# OECOC_controlbordroutes.net
KiCad netlist of a schematic drawn in EAGLE
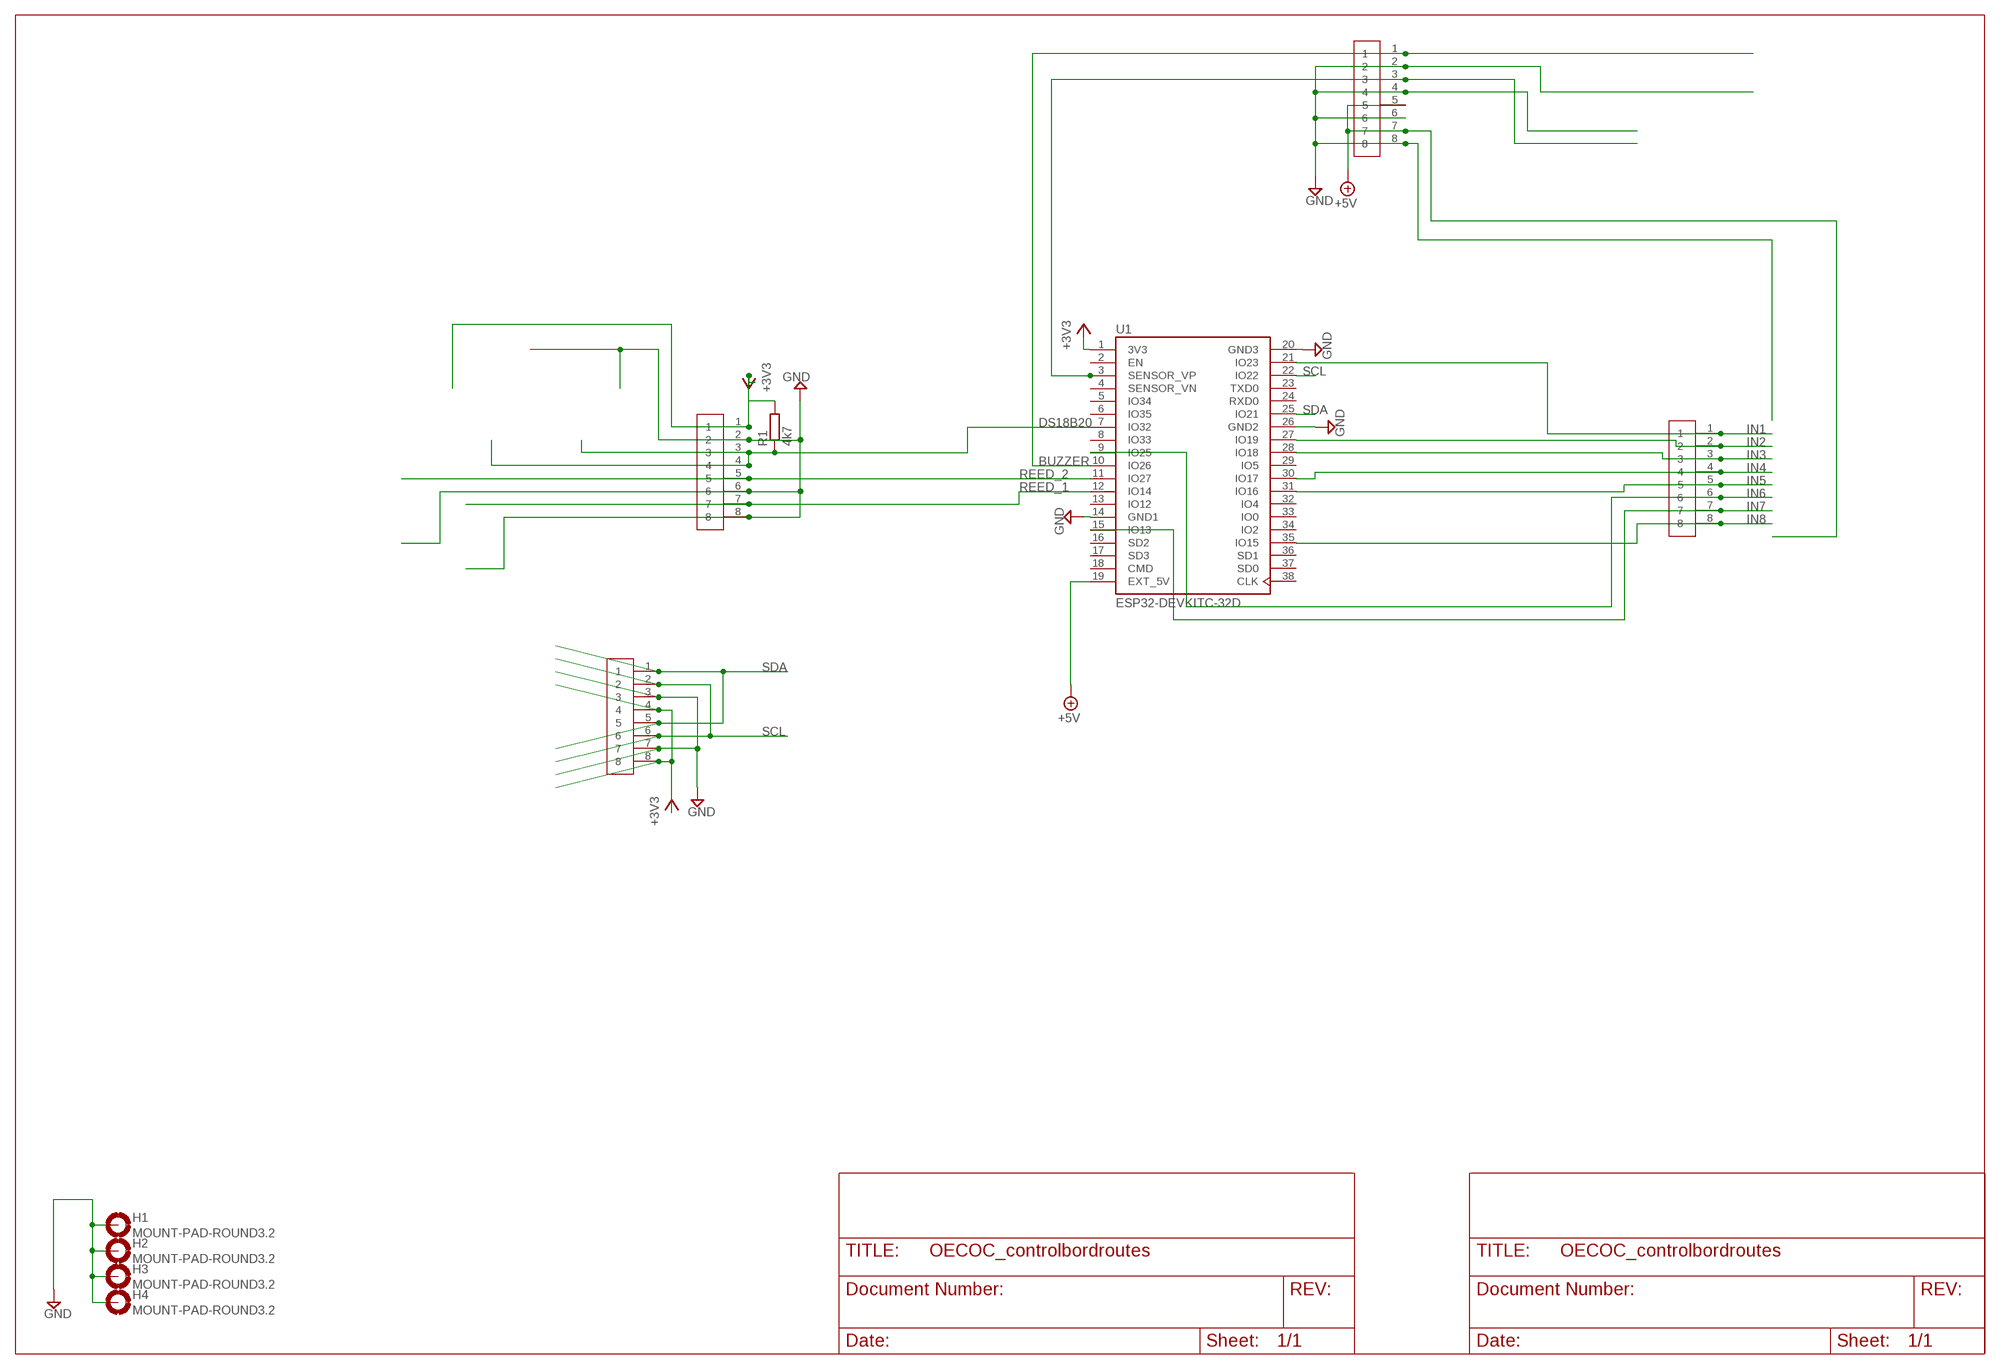
[diagram p0: schematic, sheet 1]

(export (version "E")
  (design (tool "Eeschema 10.0.6"))
  (components
    (comp (ref "H1")
      (value "MOUNT-PAD-ROUND3.2")
      (footprint "eagle-import:3,2-PAD")
      (libsource (lib "eagle-import") (part "MOUNT-PAD-ROUND3.2"))
    )
    (comp (ref "H2")
      (value "MOUNT-PAD-ROUND3.2")
      (footprint "eagle-import:3,2-PAD")
      (libsource (lib "eagle-import") (part "MOUNT-PAD-ROUND3.2"))
    )
    (comp (ref "H3")
      (value "MOUNT-PAD-ROUND3.2")
      (footprint "eagle-import:3,2-PAD")
      (libsource (lib "eagle-import") (part "MOUNT-PAD-ROUND3.2"))
    )
    (comp (ref "H4")
      (value "MOUNT-PAD-ROUND3.2")
      (footprint "eagle-import:3,2-PAD")
      (libsource (lib "eagle-import") (part "MOUNT-PAD-ROUND3.2"))
    )
    (comp (ref "R1")
      (value "4k7")
      (footprint "eagle-import:0207_10")
      (libsource (lib "eagle-import") (part "R-EU_0207/10"))
    )
    (comp (ref "U$3")
      (value "PHOENIXCONTACT_PINSTRIP")
      (footprint "eagle-import:HDRV8W150P500_1X8_2488X140X1204B")
      (libsource (lib "eagle-import") (part "PHOENIXCONTACT_PINSTRIP"))
    )
    (comp (ref "U$6")
      (value "PHOENIXCONTACT_PINSTRIP")
      (footprint "eagle-import:HDRV8W150P500_1X8_2488X140X1204B")
      (libsource (lib "eagle-import") (part "PHOENIXCONTACT_PINSTRIP"))
    )
    (comp (ref "U$7")
      (value "PHOENIXCONTACT_PINSTRIP")
      (footprint "eagle-import:HDRV8W150P500_1X8_2488X140X1204B")
      (libsource (lib "eagle-import") (part "PHOENIXCONTACT_PINSTRIP"))
    )
    (comp (ref "U$8")
      (value "PHOENIXCONTACT_PINSTRIP")
      (footprint "eagle-import:HDRV8W150P500_1X8_2488X140X1204B")
      (libsource (lib "eagle-import") (part "PHOENIXCONTACT_PINSTRIP"))
    )
    (comp (ref "U1")
      (value "ESP32-DEVKITC-32D")
      (footprint "eagle-import:MODULE_ESP32-DEVKITC-32D")
      (fields (field (name "MF") "Espressif Systems"))
      (libsource (lib "eagle-import") (part "ESP32-DEVKITC-32D"))
    )
  )
  (nets
    (net (code "1") (name "+3V3") (class "Default")
      (node (ref "R1") (pin "2") (pinfunction "2_2") (pintype "passive"))
      (node (ref "U$3") (pin "4") (pinfunction "4_4") (pintype "bidirectional"))
      (node (ref "U$3") (pin "8") (pinfunction "8_8") (pintype "bidirectional"))
      (node (ref "U$6") (pin "1") (pinfunction "1_1") (pintype "bidirectional"))
      (node (ref "U1") (pin "1") (pinfunction "3V3_1") (pintype "power_in"))
    )
    (net (code "2") (name "+5V") (class "Default")
      (node (ref "U$8") (pin "5") (pinfunction "5_5") (pintype "bidirectional"))
      (node (ref "U$8") (pin "7") (pinfunction "7_7") (pintype "bidirectional"))
      (node (ref "U1") (pin "19") (pinfunction "EXT_5V_19") (pintype "power_in"))
    )
    (net (code "3") (name "/BUZZER") (class "Default")
      (node (ref "U$8") (pin "1") (pinfunction "1_1") (pintype "bidirectional"))
      (node (ref "U1") (pin "10") (pinfunction "IO26_10") (pintype "bidirectional"))
    )
    (net (code "4") (name "/DS18B20") (class "Default")
      (node (ref "R1") (pin "1") (pinfunction "1_1") (pintype "passive"))
      (node (ref "U$6") (pin "3") (pinfunction "3_3") (pintype "bidirectional"))
      (node (ref "U$6") (pin "4") (pinfunction "4_4") (pintype "bidirectional"))
      (node (ref "U1") (pin "7") (pinfunction "IO32_7") (pintype "bidirectional"))
    )
    (net (code "5") (name "/IN1") (class "Default")
      (node (ref "U$7") (pin "1") (pinfunction "1_1") (pintype "bidirectional"))
      (node (ref "U1") (pin "21") (pinfunction "IO23_21") (pintype "bidirectional"))
    )
    (net (code "6") (name "/IN2") (class "Default")
      (node (ref "U$7") (pin "2") (pinfunction "2_2") (pintype "bidirectional"))
      (node (ref "U1") (pin "27") (pinfunction "IO19_27") (pintype "bidirectional"))
    )
    (net (code "7") (name "/IN3") (class "Default")
      (node (ref "U$7") (pin "3") (pinfunction "3_3") (pintype "bidirectional"))
      (node (ref "U1") (pin "28") (pinfunction "IO18_28") (pintype "bidirectional"))
    )
    (net (code "8") (name "/IN4") (class "Default")
      (node (ref "U$7") (pin "4") (pinfunction "4_4") (pintype "bidirectional"))
      (node (ref "U1") (pin "30") (pinfunction "IO17_30") (pintype "bidirectional"))
    )
    (net (code "9") (name "/IN5") (class "Default")
      (node (ref "U$7") (pin "5") (pinfunction "5_5") (pintype "bidirectional"))
      (node (ref "U1") (pin "31") (pinfunction "IO16_31") (pintype "bidirectional"))
    )
    (net (code "10") (name "/IN6") (class "Default")
      (node (ref "U$7") (pin "6") (pinfunction "6_6") (pintype "bidirectional"))
      (node (ref "U1") (pin "9") (pinfunction "IO25_9") (pintype "bidirectional"))
    )
    (net (code "11") (name "/IN7") (class "Default")
      (node (ref "U$7") (pin "7") (pinfunction "7_7") (pintype "bidirectional"))
      (node (ref "U1") (pin "15") (pinfunction "IO13_15") (pintype "bidirectional"))
    )
    (net (code "12") (name "/IN8") (class "Default")
      (node (ref "U$7") (pin "8") (pinfunction "8_8") (pintype "bidirectional"))
      (node (ref "U1") (pin "35") (pinfunction "IO15_35") (pintype "bidirectional"))
    )
    (net (code "13") (name "/REED_1") (class "Default")
      (node (ref "U$6") (pin "7") (pinfunction "7_7") (pintype "bidirectional"))
      (node (ref "U1") (pin "12") (pinfunction "IO14_12") (pintype "bidirectional"))
    )
    (net (code "14") (name "/REED_2") (class "Default")
      (node (ref "U$6") (pin "5") (pinfunction "5_5") (pintype "bidirectional"))
      (node (ref "U1") (pin "11") (pinfunction "IO27_11") (pintype "bidirectional"))
    )
    (net (code "15") (name "/SCL") (class "Default")
      (node (ref "U$3") (pin "2") (pinfunction "2_2") (pintype "bidirectional"))
      (node (ref "U$3") (pin "6") (pinfunction "6_6") (pintype "bidirectional"))
      (node (ref "U1") (pin "22") (pinfunction "IO22_22") (pintype "bidirectional"))
    )
    (net (code "16") (name "/SDA") (class "Default")
      (node (ref "U$3") (pin "1") (pinfunction "1_1") (pintype "bidirectional"))
      (node (ref "U$3") (pin "5") (pinfunction "5_5") (pintype "bidirectional"))
      (node (ref "U1") (pin "25") (pinfunction "IO21_25") (pintype "bidirectional"))
    )
    (net (code "17") (name "GND") (class "Default")
      (node (ref "H1") (pin "B3,2") (pinfunction "MOUNT_B3,2") (pintype "passive"))
      (node (ref "H2") (pin "B3,2") (pinfunction "MOUNT_B3,2") (pintype "passive"))
      (node (ref "H3") (pin "B3,2") (pinfunction "MOUNT_B3,2") (pintype "passive"))
      (node (ref "H4") (pin "B3,2") (pinfunction "MOUNT_B3,2") (pintype "passive"))
      (node (ref "U$3") (pin "3") (pinfunction "3_3") (pintype "bidirectional"))
      (node (ref "U$3") (pin "7") (pinfunction "7_7") (pintype "bidirectional"))
      (node (ref "U$6") (pin "2") (pinfunction "2_2") (pintype "bidirectional"))
      (node (ref "U$6") (pin "6") (pinfunction "6_6") (pintype "bidirectional"))
      (node (ref "U$6") (pin "8") (pinfunction "8_8") (pintype "bidirectional"))
      (node (ref "U$8") (pin "2") (pinfunction "2_2") (pintype "bidirectional"))
      (node (ref "U$8") (pin "4") (pinfunction "4_4") (pintype "bidirectional"))
      (node (ref "U$8") (pin "6") (pinfunction "6_6") (pintype "bidirectional"))
      (node (ref "U$8") (pin "8") (pinfunction "8_8") (pintype "bidirectional"))
      (node (ref "U1") (pin "14") (pinfunction "GND1_14") (pintype "power_in"))
      (node (ref "U1") (pin "20") (pinfunction "GND3_20") (pintype "power_in"))
      (node (ref "U1") (pin "26") (pinfunction "GND2_26") (pintype "power_in"))
    )
    (net (code "18") (name "Net-(U1-SENSOR_VP)") (class "Default")
      (node (ref "U$8") (pin "3") (pinfunction "3_3") (pintype "bidirectional"))
      (node (ref "U1") (pin "3") (pinfunction "SENSOR_VP_3") (pintype "input"))
    )
    (net (code "19") (name "unconnected-(U1-CLK-Pad38)") (class "Default")
      (node (ref "U1") (pin "38") (pinfunction "CLK_38") (pintype "input"))
    )
    (net (code "20") (name "unconnected-(U1-CMD-Pad18)") (class "Default")
      (node (ref "U1") (pin "18") (pinfunction "CMD_18") (pintype "bidirectional"))
    )
    (net (code "21") (name "unconnected-(U1-EN-Pad2)") (class "Default")
      (node (ref "U1") (pin "2") (pinfunction "EN_2") (pintype "input"))
    )
    (net (code "22") (name "unconnected-(U1-IO0-Pad33)") (class "Default")
      (node (ref "U1") (pin "33") (pinfunction "IO0_33") (pintype "bidirectional"))
    )
    (net (code "23") (name "unconnected-(U1-IO2-Pad34)") (class "Default")
      (node (ref "U1") (pin "34") (pinfunction "IO2_34") (pintype "bidirectional"))
    )
    (net (code "24") (name "unconnected-(U1-IO4-Pad32)") (class "Default")
      (node (ref "U1") (pin "32") (pinfunction "IO4_32") (pintype "bidirectional"))
    )
    (net (code "25") (name "unconnected-(U1-IO5-Pad29)") (class "Default")
      (node (ref "U1") (pin "29") (pinfunction "IO5_29") (pintype "bidirectional"))
    )
    (net (code "26") (name "unconnected-(U1-IO12-Pad13)") (class "Default")
      (node (ref "U1") (pin "13") (pinfunction "IO12_13") (pintype "bidirectional"))
    )
    (net (code "27") (name "unconnected-(U1-IO33-Pad8)") (class "Default")
      (node (ref "U1") (pin "8") (pinfunction "IO33_8") (pintype "bidirectional"))
    )
    (net (code "28") (name "unconnected-(U1-IO34-Pad5)") (class "Default")
      (node (ref "U1") (pin "5") (pinfunction "IO34_5") (pintype "bidirectional"))
    )
    (net (code "29") (name "unconnected-(U1-IO35-Pad6)") (class "Default")
      (node (ref "U1") (pin "6") (pinfunction "IO35_6") (pintype "bidirectional"))
    )
    (net (code "30") (name "unconnected-(U1-RXD0-Pad24)") (class "Default")
      (node (ref "U1") (pin "24") (pinfunction "RXD0_24") (pintype "input"))
    )
    (net (code "31") (name "unconnected-(U1-SD0-Pad37)") (class "Default")
      (node (ref "U1") (pin "37") (pinfunction "SD0_37") (pintype "bidirectional"))
    )
    (net (code "32") (name "unconnected-(U1-SD1-Pad36)") (class "Default")
      (node (ref "U1") (pin "36") (pinfunction "SD1_36") (pintype "bidirectional"))
    )
    (net (code "33") (name "unconnected-(U1-SD2-Pad16)") (class "Default")
      (node (ref "U1") (pin "16") (pinfunction "SD2_16") (pintype "bidirectional"))
    )
    (net (code "34") (name "unconnected-(U1-SD3-Pad17)") (class "Default")
      (node (ref "U1") (pin "17") (pinfunction "SD3_17") (pintype "bidirectional"))
    )
    (net (code "35") (name "unconnected-(U1-SENSOR_VN-Pad4)") (class "Default")
      (node (ref "U1") (pin "4") (pinfunction "SENSOR_VN_4") (pintype "input"))
    )
    (net (code "36") (name "unconnected-(U1-TXD0-Pad23)") (class "Default")
      (node (ref "U1") (pin "23") (pinfunction "TXD0_23") (pintype "output"))
    )
  )
)
